# Main.net
KiCad netlist of a schematic drawn in Altium Designer
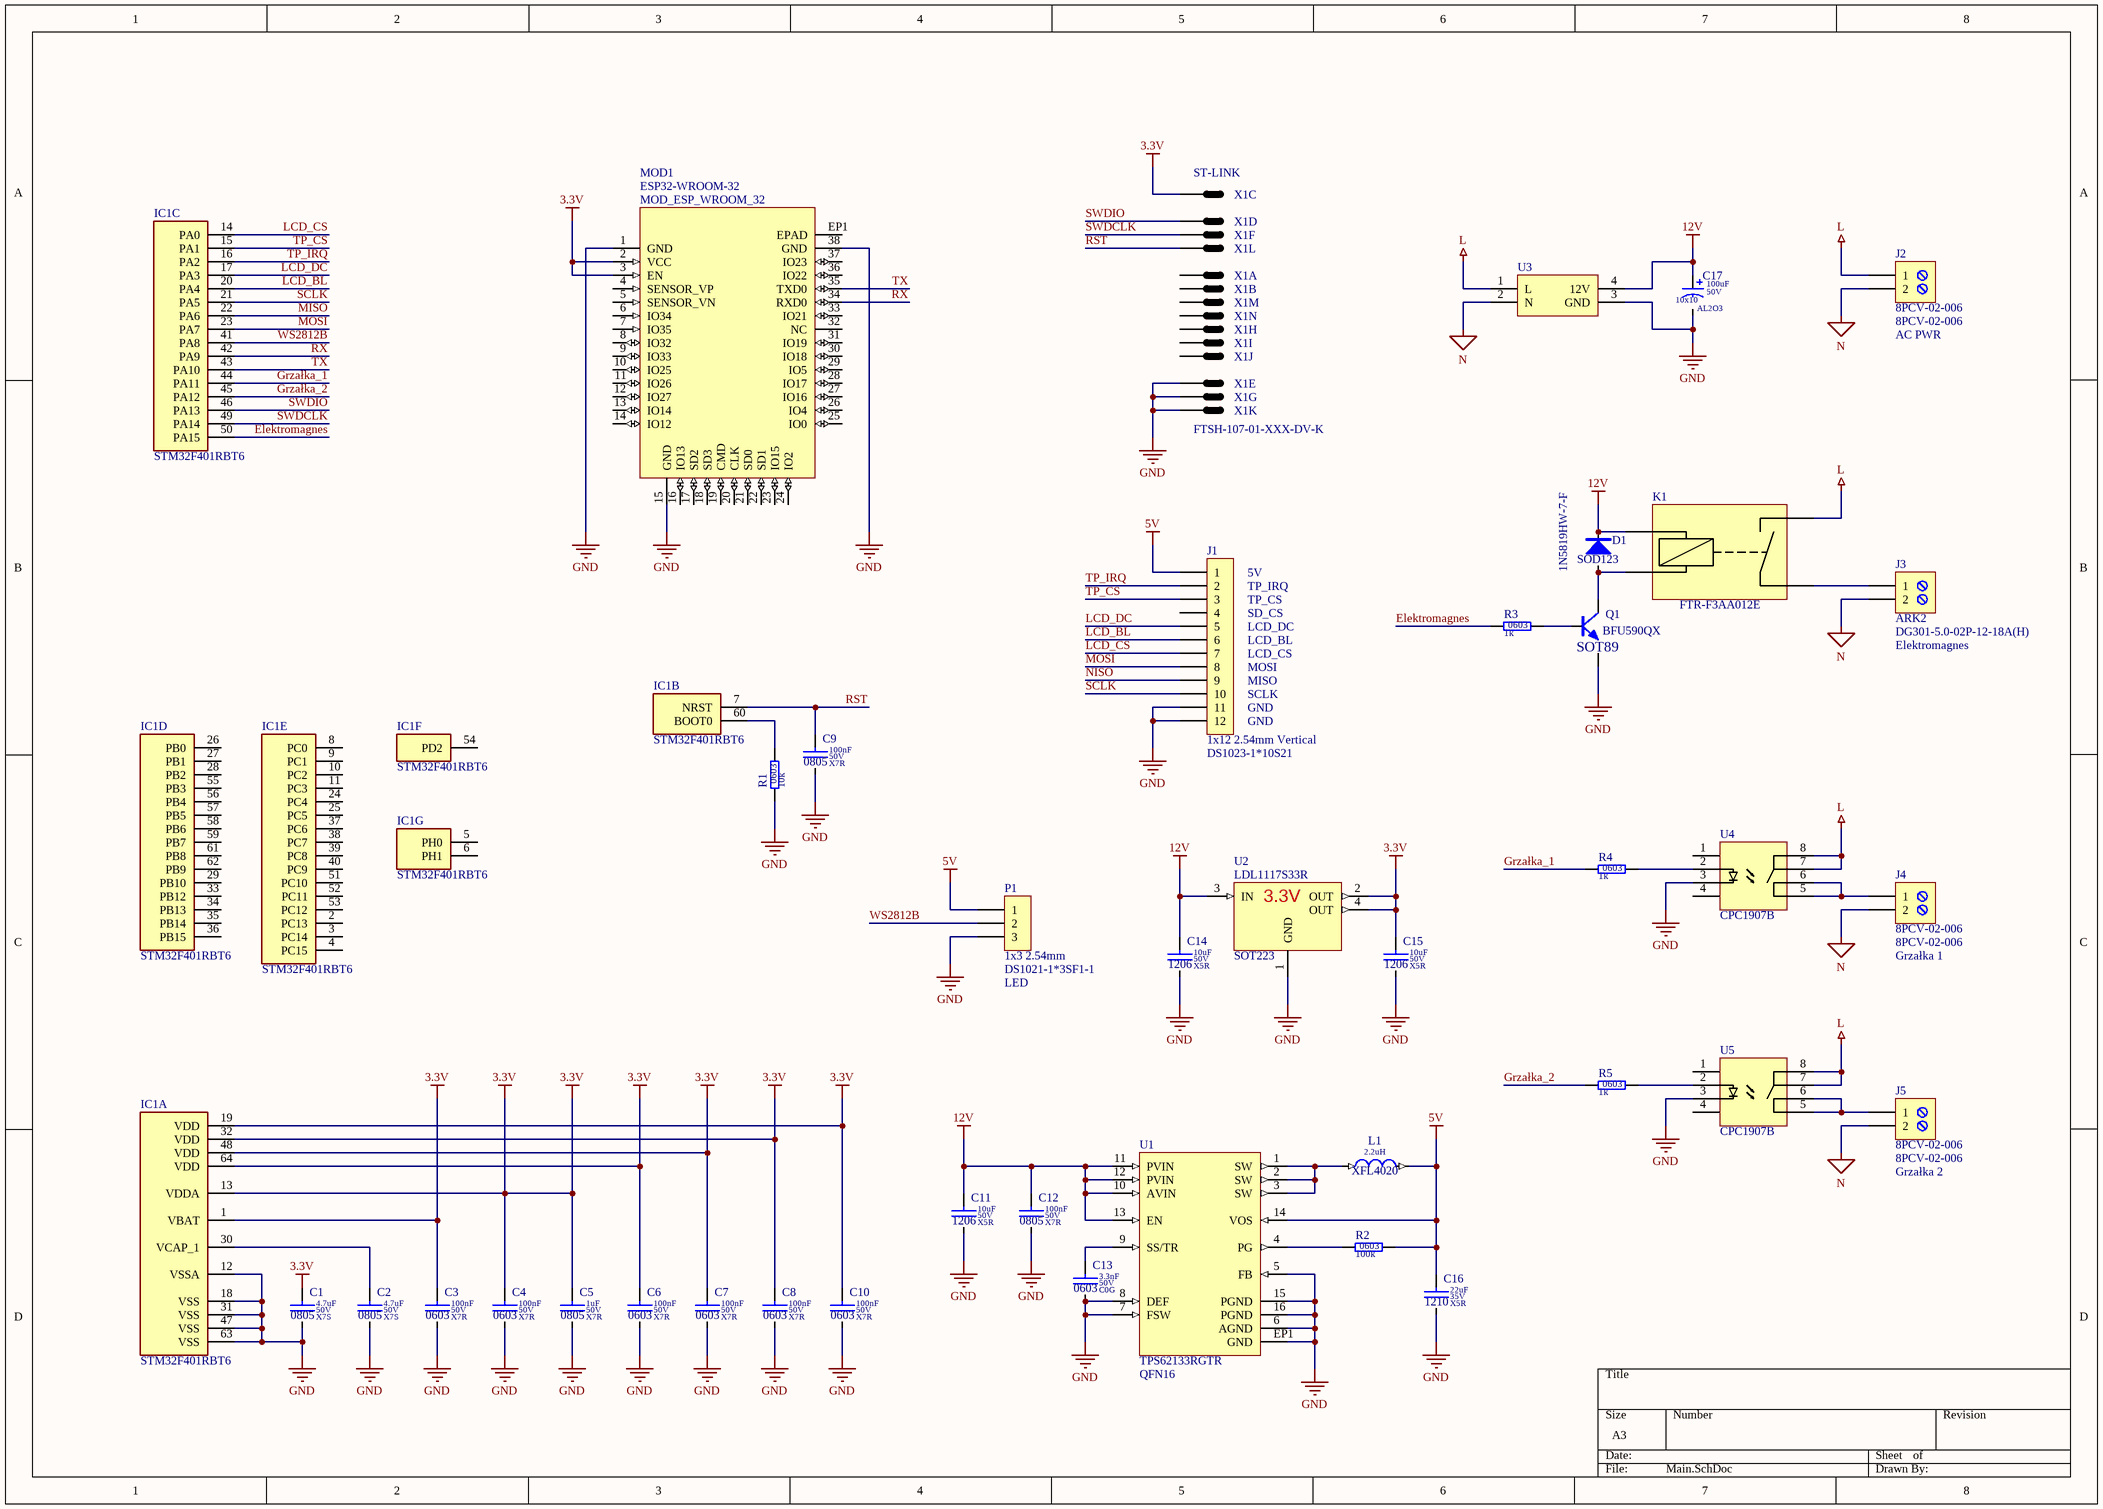
[diagram p0: Main.SchDoc]

(export (version "E")
  (design (tool "Eeschema 10.0.6"))
  (components
    (comp (ref "C1")
      (value "4.7uF")
      (footprint "C_0805_2012")
      (description "Capacitor")
      (fields
        (field (name "DIELECTRIC") "X7S")
        (field (name "VOLTAGE") "50V")
        (field (name "SCH_FOOTPRINT") "0805")
        (field (name "PART NUMBER") "C_4.7uF_50V_X7S_0805_10")
        (field (name "MANUFACTURER") "Murata")
      )
      (libsource (lib "Library") (part "C"))
    )
    (comp (ref "C2")
      (value "4.7uF")
      (footprint "C_0805_2012")
      (description "Capacitor")
      (fields
        (field (name "DIELECTRIC") "X7S")
        (field (name "VOLTAGE") "50V")
        (field (name "SCH_FOOTPRINT") "0805")
        (field (name "PART NUMBER") "C_4.7uF_50V_X7S_0805_10")
        (field (name "MANUFACTURER") "Murata")
      )
      (libsource (lib "Library") (part "C"))
    )
    (comp (ref "C3")
      (value "100nF")
      (footprint "C_0603_1608")
      (description "Capacitor")
      (fields
        (field (name "DIELECTRIC") "X7R")
        (field (name "VOLTAGE") "50V")
        (field (name "SCH_FOOTPRINT") "0603")
        (field (name "PART NUMBER") "C_100nF_50V_X7R_0603_5")
        (field (name "MANUFACTURER") "Samsung")
      )
      (libsource (lib "Library") (part "C"))
    )
    (comp (ref "C4")
      (value "100nF")
      (footprint "C_0603_1608")
      (description "Capacitor")
      (fields
        (field (name "DIELECTRIC") "X7R")
        (field (name "VOLTAGE") "50V")
        (field (name "SCH_FOOTPRINT") "0603")
        (field (name "PART NUMBER") "C_100nF_50V_X7R_0603_5")
        (field (name "MANUFACTURER") "Samsung")
      )
      (libsource (lib "Library") (part "C"))
    )
    (comp (ref "C5")
      (value "1uF")
      (footprint "C_0805_2012")
      (description "Capacitor")
      (fields
        (field (name "DIELECTRIC") "X7R")
        (field (name "VOLTAGE") "50V")
        (field (name "SCH_FOOTPRINT") "0805")
        (field (name "PART NUMBER") "C_1uF_50V_X7R_0805_10")
        (field (name "MANUFACTURER") "AVX")
      )
      (libsource (lib "Library") (part "C"))
    )
    (comp (ref "C6")
      (value "100nF")
      (footprint "C_0603_1608")
      (description "Capacitor")
      (fields
        (field (name "DIELECTRIC") "X7R")
        (field (name "VOLTAGE") "50V")
        (field (name "SCH_FOOTPRINT") "0603")
        (field (name "PART NUMBER") "C_100nF_50V_X7R_0603_5")
        (field (name "MANUFACTURER") "Samsung")
      )
      (libsource (lib "Library") (part "C"))
    )
    (comp (ref "C7")
      (value "100nF")
      (footprint "C_0603_1608")
      (description "Capacitor")
      (fields
        (field (name "DIELECTRIC") "X7R")
        (field (name "VOLTAGE") "50V")
        (field (name "SCH_FOOTPRINT") "0603")
        (field (name "PART NUMBER") "C_100nF_50V_X7R_0603_5")
        (field (name "MANUFACTURER") "Samsung")
      )
      (libsource (lib "Library") (part "C"))
    )
    (comp (ref "C8")
      (value "100nF")
      (footprint "C_0603_1608")
      (description "Capacitor")
      (fields
        (field (name "DIELECTRIC") "X7R")
        (field (name "VOLTAGE") "50V")
        (field (name "SCH_FOOTPRINT") "0603")
        (field (name "PART NUMBER") "C_100nF_50V_X7R_0603_5")
        (field (name "MANUFACTURER") "Samsung")
      )
      (libsource (lib "Library") (part "C"))
    )
    (comp (ref "C9")
      (value "100nF")
      (footprint "C_0805_2012")
      (description "Capacitor")
      (fields
        (field (name "DIELECTRIC") "X7R")
        (field (name "VOLTAGE") "50V")
        (field (name "SCH_FOOTPRINT") "0805")
        (field (name "PART NUMBER") "C_100nF_50V_X7R_0805_10")
        (field (name "MANUFACTURER") "AVX")
      )
      (libsource (lib "Library") (part "C"))
    )
    (comp (ref "C10")
      (value "100nF")
      (footprint "C_0603_1608")
      (description "Capacitor")
      (fields
        (field (name "DIELECTRIC") "X7R")
        (field (name "VOLTAGE") "50V")
        (field (name "SCH_FOOTPRINT") "0603")
        (field (name "PART NUMBER") "C_100nF_50V_X7R_0603_5")
        (field (name "MANUFACTURER") "Samsung")
      )
      (libsource (lib "Library") (part "C"))
    )
    (comp (ref "C11")
      (value "10uF")
      (footprint "C_1206_3216")
      (description "Capacitor")
      (fields
        (field (name "DIELECTRIC") "X5R")
        (field (name "VOLTAGE") "50V")
        (field (name "SCH_FOOTPRINT") "1206")
        (field (name "PART NUMBER") "C_10uF_50V_X5R_1206_10")
        (field (name "MANUFACTURER") "Murata")
      )
      (libsource (lib "Library") (part "C"))
    )
    (comp (ref "C12")
      (value "100nF")
      (footprint "C_0805_2012")
      (description "Capacitor")
      (fields
        (field (name "DIELECTRIC") "X7R")
        (field (name "VOLTAGE") "50V")
        (field (name "SCH_FOOTPRINT") "0805")
        (field (name "PART NUMBER") "C_100nF_50V_X7R_0805_10")
        (field (name "MANUFACTURER") "AVX")
      )
      (libsource (lib "Library") (part "C"))
    )
    (comp (ref "C13")
      (value "3.3nF")
      (footprint "C_0603_1608")
      (description "Capacitor")
      (fields
        (field (name "DIELECTRIC") "C0G")
        (field (name "VOLTAGE") "50V")
        (field (name "SCH_FOOTPRINT") "0603")
        (field (name "PART NUMBER") "C_3.3nF_50V_C0G_0603_5")
        (field (name "MANUFACTURER") "Murata")
      )
      (libsource (lib "Library") (part "C"))
    )
    (comp (ref "C14")
      (value "10uF")
      (footprint "C_1206_3216")
      (description "Capacitor")
      (fields
        (field (name "DIELECTRIC") "X5R")
        (field (name "VOLTAGE") "50V")
        (field (name "SCH_FOOTPRINT") "1206")
        (field (name "PART NUMBER") "C_10uF_50V_X5R_1206_10")
        (field (name "MANUFACTURER") "Murata")
      )
      (libsource (lib "Library") (part "C"))
    )
    (comp (ref "C15")
      (value "10uF")
      (footprint "C_1206_3216")
      (description "Capacitor")
      (fields
        (field (name "DIELECTRIC") "X5R")
        (field (name "VOLTAGE") "50V")
        (field (name "SCH_FOOTPRINT") "1206")
        (field (name "PART NUMBER") "C_10uF_50V_X5R_1206_10")
        (field (name "MANUFACTURER") "Murata")
      )
      (libsource (lib "Library") (part "C"))
    )
    (comp (ref "C16")
      (value "22uF")
      (footprint "C_1210_3225")
      (description "Capacitor")
      (fields
        (field (name "DIELECTRIC") "X5R")
        (field (name "VOLTAGE") "35V")
        (field (name "SCH_FOOTPRINT") "1210")
        (field (name "PART NUMBER") "C_22uF_35V_X5R_1210_20")
        (field (name "MANUFACTURER") "Taiyo Yuden")
      )
      (libsource (lib "Library") (part "C"))
    )
    (comp (ref "C17")
      (value "100uF")
      (footprint "CE_D_10x10_SMD")
      (description "Polarized Capacitor")
      (fields
        (field (name "DIELECTRIC") "AL2O3")
        (field (name "SCH_FOOTPRINT") "10x10")
        (field (name "VOLTAGE") "50V")
        (field (name "PART NUMBER") "CE_100uF_50V_AL2O3_10x10_20")
        (field (name "MANUFACTURER") "Nichicon")
      )
      (libsource (lib "Library") (part "CE"))
    )
    (comp (ref "D1")
      (value "1N5819HW-7-F")
      (footprint "SOD123")
      (fields
        (field (name "SCH_FOOTPRINT") "SOD123")
        (field (name "PART NUMBER") "D_1N5819HW_1A_40V_SOD123")
        (field (name "VOLTAGE") "40V")
        (field (name "MANUFACTURER") "Diodes Inc")
      )
      (libsource (lib "Library") (part "D"))
    )
    (comp (ref "IC1")
      (value "STM32F401RBT6")
      (footprint "LQFP-64")
      (description "ARM Microcontroller")
      (libsource (lib "Components") (part "STM32F401RBT6"))
    )
    (comp (ref "J1")
      (value "DS1023-1*10S21")
      (footprint "J_HEADER_1x12_2.54_VERTICAL")
      (description "Pin Header")
      (fields
        (field (name "SCH_FOOTPRINT") "1x12 2.54mm Vertical")
        (field (name "PART NUMBER") "J_HEADER_1x12_2.54_VERTICAL")
        (field (name "MANUFACTURER") "Connfly")
      )
      (libsource (lib "Library") (part "J_HEADER_1x12"))
    )
    (comp (ref "J2")
      (value "8PCV-02-006")
      (footprint "J_8PCV-02-006")
      (description "ARK Screw terminal, 2-Pin")
      (fields
        (field (name "SCH_FOOTPRINT") "8PCV-02-006")
        (field (name "PART NUMBER") "J_8PCV-02-006")
        (field (name "MANUFACTURER") "TE Connectivity")
      )
      (libsource (lib "Library") (part "J_ARK2"))
    )
    (comp (ref "J3")
      (value "DG301-5.0-02P-12-18A(H)")
      (footprint "J_ARK2")
      (description "ARK Screw terminal, 2-Pin")
      (fields
        (field (name "SCH_FOOTPRINT") "ARK2")
        (field (name "PART NUMBER") "J_TB-5.0-P-2P")
        (field (name "MANUFACTURER") "DEGSON ELECTRONICS")
      )
      (libsource (lib "Library") (part "J_ARK2"))
    )
    (comp (ref "J4")
      (value "8PCV-02-006")
      (footprint "J_8PCV-02-006")
      (description "ARK Screw terminal, 2-Pin")
      (fields
        (field (name "SCH_FOOTPRINT") "8PCV-02-006")
        (field (name "PART NUMBER") "J_8PCV-02-006")
        (field (name "MANUFACTURER") "TE Connectivity")
      )
      (libsource (lib "Library") (part "J_ARK2"))
    )
    (comp (ref "J5")
      (value "8PCV-02-006")
      (footprint "J_8PCV-02-006")
      (description "ARK Screw terminal, 2-Pin")
      (fields
        (field (name "SCH_FOOTPRINT") "8PCV-02-006")
        (field (name "PART NUMBER") "J_8PCV-02-006")
        (field (name "MANUFACTURER") "TE Connectivity")
      )
      (libsource (lib "Library") (part "J_ARK2"))
    )
    (comp (ref "K1")
      (value "FTR-F3AA012E")
      (footprint "FTR-F3AA012E")
      (libsource (lib "SchLib") (part "FTR-F3AA012E"))
    )
    (comp (ref "L1")
      (value "2.2uH")
      (footprint "XFL4020")
      (description "Induction")
      (fields
        (field (name "SCH_FOOTPRINT") "XFL4020")
        (field (name "PART NUMBER") "L_2.2uH_8A_XFL4020")
        (field (name "MANUFACTURER") "Coilcraft")
      )
      (libsource (lib "Library") (part "L"))
    )
    (comp (ref "MOD1")
      (value "ESP32-WROOM-32")
      (footprint "MOD_ESP_WROOM_32")
      (fields
        (field (name "SCH_FOOTPRINT") "MOD_ESP_WROOM_32")
        (field (name "PART NUMBER") "MOD_ESP32-WROOM-32")
        (field (name "MANUFACTURER") "ESPRESSIF")
        (field (name "Comment") "2.4 GHz Wi-Fi-and-Bluetooth combo chip")
      )
      (libsource (lib "Library") (part "MOD_ESP_WROOM_32"))
    )
    (comp (ref "P1")
      (value "DS1021-1*3SF1-1")
      (footprint "P_HEADER_1x3_2.54")
      (description "Pin Header")
      (fields
        (field (name "SCH_FOOTPRINT") "1x3 2.54mm")
        (field (name "PART NUMBER") "P_HEADER_1x3_2.54")
        (field (name "MANUFACTURER") "Connfly")
      )
      (libsource (lib "Library") (part "P_HEADER_1x3"))
    )
    (comp (ref "Q1")
      (value "BFU590QX")
      (footprint "SOT89_TO-243AA_N")
      (fields
        (field (name "SCH_FOOTPRINT") "SOT89")
        (field (name "PART NUMBER") "QNP_BFU590QX")
        (field (name "VOLTAGE") "12V")
        (field (name "MANUFACTURER") "NXP")
      )
      (libsource (lib "Library") (part "QNP_ECB"))
    )
    (comp (ref "R1")
      (value "10k")
      (footprint "R_0603_1608")
      (fields
        (field (name "SCH_FOOTPRINT") "0603")
        (field (name "PART NUMBER") "R_10k_0603_1")
        (field (name "VOLTAGE") "75V")
        (field (name "POWER") "100mW")
      )
      (libsource (lib "Library") (part "R"))
    )
    (comp (ref "R2")
      (value "100k")
      (footprint "R_0603_1608")
      (fields
        (field (name "SCH_FOOTPRINT") "0603")
        (field (name "PART NUMBER") "R_100k_0603_1")
        (field (name "VOLTAGE") "50V")
        (field (name "POWER") "100mW")
      )
      (libsource (lib "Library") (part "R"))
    )
    (comp (ref "R3")
      (value "1k")
      (footprint "R_0603_1608")
      (fields
        (field (name "SCH_FOOTPRINT") "0603")
        (field (name "PART NUMBER") "R_1k_0603_1")
        (field (name "VOLTAGE") "75V")
        (field (name "POWER") "100mW")
      )
      (libsource (lib "Library") (part "R"))
    )
    (comp (ref "R4")
      (value "1k")
      (footprint "R_0603_1608")
      (fields
        (field (name "SCH_FOOTPRINT") "0603")
        (field (name "PART NUMBER") "R_1k_0603_1")
        (field (name "VOLTAGE") "75V")
        (field (name "POWER") "100mW")
      )
      (libsource (lib "Library") (part "R"))
    )
    (comp (ref "R5")
      (value "1k")
      (footprint "R_0603_1608")
      (fields
        (field (name "SCH_FOOTPRINT") "0603")
        (field (name "PART NUMBER") "R_1k_0603_1")
        (field (name "VOLTAGE") "75V")
        (field (name "POWER") "100mW")
      )
      (libsource (lib "Library") (part "R"))
    )
    (comp (ref "U1")
      (value "TPS62133RGTR")
      (footprint "QFN16_3x3")
      (description "3-17V 3A Step-Down Converter with DCS-Control in 3x3 QFN")
      (fields
        (field (name "SCH_FOOTPRINT") "QFN16")
        (field (name "PART NUMBER") "VS_TPS62133RGTR")
        (field (name "MANUFACTURER") "Texas Instruments")
      )
      (libsource (lib "Library") (part "VS_TPS6213x"))
    )
    (comp (ref "U2")
      (value "LDL1117S33R")
      (footprint "SOT223_SC73")
      (description "typical configuration")
      (fields
        (field (name "SCH_FOOTPRINT") "SOT223")
        (field (name "PART NUMBER") "VL_LDL1117S33R")
        (field (name "VOLTAGE") "3.3V")
      )
      (libsource (lib "Library") (part "VL_4pin_3_1_2,4"))
    )
    (comp (ref "U3")
      (value "IRM-30-12")
      (footprint "IRM-30-12")
      (libsource (lib "SchLib") (part "IRM-30-12"))
    )
    (comp (ref "U4") (value "CPC1907B") (footprint "CPC1907B") (libsource (lib "SchLib") (part "CPC1907B")))
    (comp (ref "U5") (value "CPC1907B") (footprint "CPC1907B") (libsource (lib "SchLib") (part "CPC1907B")))
    (comp (ref "X1")
      (value "FTSH-107-01-XXX-DV-K")
      (footprint "FTSH-107-01-XXX-DV-K")
      (description "IDC 14pin male connector")
      (libsource (lib "Connectors") (part "FTSH-107-01-XXX-DV-K"))
    )
  )
  (nets
    (net (code "1") (name "/Elektromagnes") (class "Default")
      (node (ref "IC1") (pin "50") (pinfunction "PA15_50") (pintype "passive"))
      (node (ref "R3") (pin "1") (pinfunction "1_1") (pintype "passive"))
    )
    (net (code "2") (name "/Grzałka_1") (class "Default")
      (node (ref "IC1") (pin "44") (pinfunction "PA11_44") (pintype "passive"))
      (node (ref "R4") (pin "1") (pinfunction "1_1") (pintype "passive"))
    )
    (net (code "3") (name "/Grzałka_2") (class "Default")
      (node (ref "IC1") (pin "45") (pinfunction "PA12_45") (pintype "passive"))
      (node (ref "R5") (pin "1") (pinfunction "1_1") (pintype "passive"))
    )
    (net (code "4") (name "/LCD_BL") (class "Default")
      (node (ref "IC1") (pin "20") (pinfunction "PA4_20") (pintype "passive"))
      (node (ref "J1") (pin "6") (pinfunction "6_6") (pintype "passive"))
    )
    (net (code "5") (name "/LCD_CS") (class "Default")
      (node (ref "IC1") (pin "14") (pinfunction "PA0_14") (pintype "passive"))
      (node (ref "J1") (pin "7") (pinfunction "7_7") (pintype "passive"))
    )
    (net (code "6") (name "/LCD_DC") (class "Default")
      (node (ref "IC1") (pin "17") (pinfunction "PA3_17") (pintype "passive"))
      (node (ref "J1") (pin "5") (pinfunction "5_5") (pintype "passive"))
    )
    (net (code "7") (name "/MISO") (class "Default")
      (node (ref "IC1") (pin "22") (pinfunction "PA6_22") (pintype "passive"))
    )
    (net (code "8") (name "/MOSI") (class "Default")
      (node (ref "IC1") (pin "23") (pinfunction "PA7_23") (pintype "passive"))
      (node (ref "J1") (pin "8") (pinfunction "8_8") (pintype "passive"))
    )
    (net (code "9") (name "/NISO") (class "Default")
      (node (ref "J1") (pin "9") (pinfunction "9_9") (pintype "passive"))
    )
    (net (code "10") (name "/RST") (class "Default")
      (node (ref "C9") (pin "1") (pinfunction "1_1") (pintype "passive"))
      (node (ref "IC1") (pin "7") (pinfunction "NRST_7") (pintype "passive"))
      (node (ref "X1") (pin "12") (pinfunction "12_12") (pintype "passive"))
    )
    (net (code "11") (name "/RX") (class "Default")
      (node (ref "IC1") (pin "42") (pinfunction "PA9_42") (pintype "passive"))
      (node (ref "MOD1") (pin "34") (pinfunction "RXD0_34") (pintype "bidirectional"))
    )
    (net (code "12") (name "/SCLK") (class "Default")
      (node (ref "IC1") (pin "21") (pinfunction "PA5_21") (pintype "passive"))
      (node (ref "J1") (pin "10") (pinfunction "10_10") (pintype "passive"))
    )
    (net (code "13") (name "/SWDCLK") (class "Default")
      (node (ref "IC1") (pin "49") (pinfunction "PA14_49") (pintype "passive"))
      (node (ref "X1") (pin "6") (pinfunction "6_6") (pintype "passive"))
    )
    (net (code "14") (name "/SWDIO") (class "Default")
      (node (ref "IC1") (pin "46") (pinfunction "PA13_46") (pintype "passive"))
      (node (ref "X1") (pin "4") (pinfunction "4_4") (pintype "passive"))
    )
    (net (code "15") (name "/TP_CS") (class "Default")
      (node (ref "IC1") (pin "15") (pinfunction "PA1_15") (pintype "passive"))
      (node (ref "J1") (pin "3") (pinfunction "3_3") (pintype "passive"))
    )
    (net (code "16") (name "/TP_IRQ") (class "Default")
      (node (ref "IC1") (pin "16") (pinfunction "PA2_16") (pintype "passive"))
      (node (ref "J1") (pin "2") (pinfunction "2_2") (pintype "passive"))
    )
    (net (code "17") (name "/TX") (class "Default")
      (node (ref "IC1") (pin "43") (pinfunction "PA10_43") (pintype "passive"))
      (node (ref "MOD1") (pin "35") (pinfunction "TXD0_35") (pintype "bidirectional"))
    )
    (net (code "18") (name "/WS2812B") (class "Default")
      (node (ref "IC1") (pin "41") (pinfunction "PA8_41") (pintype "passive"))
      (node (ref "P1") (pin "2") (pinfunction "2_2") (pintype "passive"))
    )
    (net (code "19") (name "3.3V") (class "Default")
      (node (ref "C1") (pin "1") (pinfunction "1_1") (pintype "passive"))
      (node (ref "C10") (pin "1") (pinfunction "1_1") (pintype "passive"))
      (node (ref "C15") (pin "1") (pinfunction "1_1") (pintype "passive"))
      (node (ref "C3") (pin "1") (pinfunction "1_1") (pintype "passive"))
      (node (ref "C4") (pin "1") (pinfunction "1_1") (pintype "passive"))
      (node (ref "C5") (pin "1") (pinfunction "1_1") (pintype "passive"))
      (node (ref "C6") (pin "1") (pinfunction "1_1") (pintype "passive"))
      (node (ref "C7") (pin "1") (pinfunction "1_1") (pintype "passive"))
      (node (ref "C8") (pin "1") (pinfunction "1_1") (pintype "passive"))
      (node (ref "IC1") (pin "1") (pinfunction "VBAT_1") (pintype "passive"))
      (node (ref "IC1") (pin "13") (pinfunction "VDDA_13") (pintype "passive"))
      (node (ref "IC1") (pin "19") (pinfunction "VDD_19") (pintype "passive"))
      (node (ref "IC1") (pin "32") (pinfunction "VDD_32") (pintype "passive"))
      (node (ref "IC1") (pin "48") (pinfunction "VDD_48") (pintype "passive"))
      (node (ref "IC1") (pin "64") (pinfunction "VDD_64") (pintype "passive"))
      (node (ref "MOD1") (pin "2") (pinfunction "VCC_2") (pintype "input"))
      (node (ref "MOD1") (pin "3") (pinfunction "EN_3") (pintype "input"))
      (node (ref "U2") (pin "2") (pinfunction "OUT_2") (pintype "output"))
      (node (ref "U2") (pin "4") (pinfunction "OUT_4") (pintype "output"))
      (node (ref "X1") (pin "3") (pinfunction "3_3") (pintype "passive"))
    )
    (net (code "20") (name "5V") (class "Default")
      (node (ref "C16") (pin "1") (pinfunction "1_1") (pintype "passive"))
      (node (ref "J1") (pin "1") (pinfunction "1_1") (pintype "passive"))
      (node (ref "L1") (pin "2") (pinfunction "2_2") (pintype "output"))
      (node (ref "P1") (pin "1") (pinfunction "1_1") (pintype "passive"))
      (node (ref "R2") (pin "2") (pinfunction "2_2") (pintype "passive"))
      (node (ref "U1") (pin "14") (pinfunction "VOS_14") (pintype "input"))
    )
    (net (code "21") (name "12V") (class "Default")
      (node (ref "C11") (pin "1") (pinfunction "1_1") (pintype "passive"))
      (node (ref "C12") (pin "1") (pinfunction "1_1") (pintype "passive"))
      (node (ref "C14") (pin "1") (pinfunction "1_1") (pintype "passive"))
      (node (ref "C17") (pin "1") (pinfunction "1_1") (pintype "passive"))
      (node (ref "D1") (pin "1") (pintype "passive"))
      (node (ref "K1") (pin "1") (pinfunction "1_1") (pintype "passive"))
      (node (ref "U1") (pin "10") (pinfunction "AVIN_10") (pintype "input"))
      (node (ref "U1") (pin "11") (pinfunction "PVIN_11") (pintype "input"))
      (node (ref "U1") (pin "12") (pinfunction "PVIN_12") (pintype "input"))
      (node (ref "U1") (pin "13") (pinfunction "EN_13") (pintype "input"))
      (node (ref "U2") (pin "3") (pinfunction "IN_3") (pintype "input"))
      (node (ref "U3") (pin "4") (pinfunction "12V_4") (pintype "passive"))
    )
    (net (code "22") (name "GND") (class "Default")
      (node (ref "C1") (pin "2") (pinfunction "2_2") (pintype "passive"))
      (node (ref "C10") (pin "2") (pinfunction "2_2") (pintype "passive"))
      (node (ref "C11") (pin "2") (pinfunction "2_2") (pintype "passive"))
      (node (ref "C12") (pin "2") (pinfunction "2_2") (pintype "passive"))
      (node (ref "C13") (pin "2") (pinfunction "2_2") (pintype "passive"))
      (node (ref "C14") (pin "2") (pinfunction "2_2") (pintype "passive"))
      (node (ref "C15") (pin "2") (pinfunction "2_2") (pintype "passive"))
      (node (ref "C16") (pin "2") (pinfunction "2_2") (pintype "passive"))
      (node (ref "C17") (pin "2") (pinfunction "2_2") (pintype "passive"))
      (node (ref "C2") (pin "2") (pinfunction "2_2") (pintype "passive"))
      (node (ref "C3") (pin "2") (pinfunction "2_2") (pintype "passive"))
      (node (ref "C4") (pin "2") (pinfunction "2_2") (pintype "passive"))
      (node (ref "C5") (pin "2") (pinfunction "2_2") (pintype "passive"))
      (node (ref "C6") (pin "2") (pinfunction "2_2") (pintype "passive"))
      (node (ref "C7") (pin "2") (pinfunction "2_2") (pintype "passive"))
      (node (ref "C8") (pin "2") (pinfunction "2_2") (pintype "passive"))
      (node (ref "C9") (pin "2") (pinfunction "2_2") (pintype "passive"))
      (node (ref "IC1") (pin "12") (pinfunction "VSSA_12") (pintype "passive"))
      (node (ref "IC1") (pin "18") (pinfunction "VSS_18") (pintype "passive"))
      (node (ref "IC1") (pin "31") (pinfunction "VSS_31") (pintype "passive"))
      (node (ref "IC1") (pin "47") (pinfunction "VSS_47") (pintype "passive"))
      (node (ref "IC1") (pin "63") (pinfunction "VSS_63") (pintype "passive"))
      (node (ref "J1") (pin "11") (pinfunction "11_11") (pintype "passive"))
      (node (ref "J1") (pin "12") (pinfunction "12_12") (pintype "passive"))
      (node (ref "MOD1") (pin "1") (pinfunction "GND_1") (pintype "power_in"))
      (node (ref "MOD1") (pin "15") (pinfunction "GND_15") (pintype "power_in"))
      (node (ref "MOD1") (pin "38") (pinfunction "GND_38") (pintype "power_in"))
      (node (ref "P1") (pin "3") (pinfunction "3_3") (pintype "passive"))
      (node (ref "Q1") (pin "1") (pinfunction "E_1") (pintype "passive"))
      (node (ref "R1") (pin "1") (pinfunction "1_1") (pintype "passive"))
      (node (ref "U1") (pin "15") (pinfunction "PGND_15") (pintype "power_in"))
      (node (ref "U1") (pin "16") (pinfunction "PGND_16") (pintype "power_in"))
      (node (ref "U1") (pin "5") (pinfunction "FB_5") (pintype "input"))
      (node (ref "U1") (pin "6") (pinfunction "AGND_6") (pintype "power_in"))
      (node (ref "U1") (pin "7") (pinfunction "FSW_7") (pintype "input"))
      (node (ref "U1") (pin "8") (pinfunction "DEF_8") (pintype "input"))
      (node (ref "U1") (pin "EP1") (pinfunction "GND_EP1") (pintype "power_in"))
      (node (ref "U2") (pin "1") (pinfunction "GND_1") (pintype "power_in"))
      (node (ref "U3") (pin "3") (pinfunction "GND_3") (pintype "passive"))
      (node (ref "U4") (pin "3") (pinfunction "3_3") (pintype "passive"))
      (node (ref "U5") (pin "3") (pinfunction "3_3") (pintype "passive"))
      (node (ref "X1") (pin "11") (pinfunction "11_11") (pintype "passive"))
      (node (ref "X1") (pin "5") (pinfunction "5_5") (pintype "passive"))
      (node (ref "X1") (pin "7") (pinfunction "7_7") (pintype "passive"))
    )
    (net (code "23") (name "L") (class "Default")
      (node (ref "J2") (pin "1") (pinfunction "1_1") (pintype "passive"))
      (node (ref "K1") (pin "3") (pinfunction "3_3") (pintype "passive"))
      (node (ref "U3") (pin "1") (pinfunction "L_1") (pintype "passive"))
      (node (ref "U4") (pin "7") (pinfunction "7_7") (pintype "passive"))
      (node (ref "U4") (pin "8") (pinfunction "8_8") (pintype "passive"))
      (node (ref "U5") (pin "7") (pinfunction "7_7") (pintype "passive"))
      (node (ref "U5") (pin "8") (pinfunction "8_8") (pintype "passive"))
    )
    (net (code "24") (name "N") (class "Default")
      (node (ref "J2") (pin "2") (pinfunction "2_2") (pintype "passive"))
      (node (ref "J3") (pin "2") (pinfunction "2_2") (pintype "passive"))
      (node (ref "J4") (pin "2") (pinfunction "2_2") (pintype "passive"))
      (node (ref "J5") (pin "2") (pinfunction "2_2") (pintype "passive"))
      (node (ref "U3") (pin "2") (pinfunction "N_2") (pintype "passive"))
    )
    (net (code "25") (name "Net-(IC1A-VCAP_1)") (class "Default")
      (node (ref "C2") (pin "1") (pinfunction "1_1") (pintype "passive"))
      (node (ref "IC1") (pin "30") (pinfunction "VCAP_1_30") (pintype "passive"))
    )
    (net (code "26") (name "Net-(IC1B-BOOT0)") (class "Default")
      (node (ref "IC1") (pin "60") (pinfunction "BOOT0_60") (pintype "passive"))
      (node (ref "R1") (pin "2") (pinfunction "2_2") (pintype "passive"))
    )
    (net (code "27") (name "Net-(J3-Pad1)") (class "Default")
      (node (ref "J3") (pin "1") (pinfunction "1_1") (pintype "passive"))
      (node (ref "K1") (pin "4") (pinfunction "4_4") (pintype "passive"))
    )
    (net (code "28") (name "Net-(J4-Pad1)") (class "Default")
      (node (ref "J4") (pin "1") (pinfunction "1_1") (pintype "passive"))
      (node (ref "U4") (pin "5") (pinfunction "5_5") (pintype "passive"))
      (node (ref "U4") (pin "6") (pinfunction "6_6") (pintype "passive"))
    )
    (net (code "29") (name "Net-(J5-Pad1)") (class "Default")
      (node (ref "J5") (pin "1") (pinfunction "1_1") (pintype "passive"))
      (node (ref "U5") (pin "5") (pinfunction "5_5") (pintype "passive"))
      (node (ref "U5") (pin "6") (pinfunction "6_6") (pintype "passive"))
    )
    (net (code "30") (name "Net-(L1-Pad1)") (class "Default")
      (node (ref "L1") (pin "1") (pinfunction "1_1") (pintype "input"))
      (node (ref "U1") (pin "1") (pinfunction "SW_1") (pintype "output"))
      (node (ref "U1") (pin "2") (pinfunction "SW_2") (pintype "output"))
      (node (ref "U1") (pin "3") (pinfunction "SW_3") (pintype "output"))
    )
    (net (code "31") (name "Net-(Q1-B)") (class "Default")
      (node (ref "Q1") (pin "3") (pinfunction "B_3") (pintype "passive"))
      (node (ref "R3") (pin "2") (pinfunction "2_2") (pintype "passive"))
    )
    (net (code "32") (name "Net-(Q1-C)") (class "Default")
      (node (ref "D1") (pin "2") (pintype "passive"))
      (node (ref "K1") (pin "2") (pinfunction "2_2") (pintype "passive"))
      (node (ref "Q1") (pin "2") (pinfunction "C_2") (pintype "passive"))
    )
    (net (code "33") (name "Net-(R4-Pad2)") (class "Default")
      (node (ref "R4") (pin "2") (pinfunction "2_2") (pintype "passive"))
      (node (ref "U4") (pin "2") (pinfunction "2_2") (pintype "passive"))
    )
    (net (code "34") (name "Net-(R5-Pad2)") (class "Default")
      (node (ref "R5") (pin "2") (pinfunction "2_2") (pintype "passive"))
      (node (ref "U5") (pin "2") (pinfunction "2_2") (pintype "passive"))
    )
    (net (code "35") (name "Net-(U1-PG)") (class "Default")
      (node (ref "R2") (pin "1") (pinfunction "1_1") (pintype "passive"))
      (node (ref "U1") (pin "4") (pinfunction "PG_4") (pintype "output"))
    )
    (net (code "36") (name "Net-(U1-SS{slash}TR)") (class "Default")
      (node (ref "C13") (pin "1") (pinfunction "1_1") (pintype "passive"))
      (node (ref "U1") (pin "9") (pinfunction "SS/TR_9") (pintype "input"))
    )
    (net (code "37") (name "unconnected-(IC1D-PB0-Pad26)") (class "Default")
      (node (ref "IC1") (pin "26") (pinfunction "PB0_26") (pintype "passive"))
    )
    (net (code "38") (name "unconnected-(IC1D-PB1-Pad27)") (class "Default")
      (node (ref "IC1") (pin "27") (pinfunction "PB1_27") (pintype "passive"))
    )
    (net (code "39") (name "unconnected-(IC1D-PB2-Pad28)") (class "Default")
      (node (ref "IC1") (pin "28") (pinfunction "PB2_28") (pintype "passive"))
    )
    (net (code "40") (name "unconnected-(IC1D-PB3-Pad55)") (class "Default")
      (node (ref "IC1") (pin "55") (pinfunction "PB3_55") (pintype "passive"))
    )
    (net (code "41") (name "unconnected-(IC1D-PB4-Pad56)") (class "Default")
      (node (ref "IC1") (pin "56") (pinfunction "PB4_56") (pintype "passive"))
    )
    (net (code "42") (name "unconnected-(IC1D-PB5-Pad57)") (class "Default")
      (node (ref "IC1") (pin "57") (pinfunction "PB5_57") (pintype "passive"))
    )
    (net (code "43") (name "unconnected-(IC1D-PB6-Pad58)") (class "Default")
      (node (ref "IC1") (pin "58") (pinfunction "PB6_58") (pintype "passive"))
    )
    (net (code "44") (name "unconnected-(IC1D-PB7-Pad59)") (class "Default")
      (node (ref "IC1") (pin "59") (pinfunction "PB7_59") (pintype "passive"))
    )
    (net (code "45") (name "unconnected-(IC1D-PB8-Pad61)") (class "Default")
      (node (ref "IC1") (pin "61") (pinfunction "PB8_61") (pintype "passive"))
    )
    (net (code "46") (name "unconnected-(IC1D-PB9-Pad62)") (class "Default")
      (node (ref "IC1") (pin "62") (pinfunction "PB9_62") (pintype "passive"))
    )
    (net (code "47") (name "unconnected-(IC1D-PB10-Pad29)") (class "Default")
      (node (ref "IC1") (pin "29") (pinfunction "PB10_29") (pintype "passive"))
    )
    (net (code "48") (name "unconnected-(IC1D-PB12-Pad33)") (class "Default")
      (node (ref "IC1") (pin "33") (pinfunction "PB12_33") (pintype "passive"))
    )
    (net (code "49") (name "unconnected-(IC1D-PB13-Pad34)") (class "Default")
      (node (ref "IC1") (pin "34") (pinfunction "PB13_34") (pintype "passive"))
    )
    (net (code "50") (name "unconnected-(IC1D-PB14-Pad35)") (class "Default")
      (node (ref "IC1") (pin "35") (pinfunction "PB14_35") (pintype "passive"))
    )
    (net (code "51") (name "unconnected-(IC1D-PB15-Pad36)") (class "Default")
      (node (ref "IC1") (pin "36") (pinfunction "PB15_36") (pintype "passive"))
    )
    (net (code "52") (name "unconnected-(IC1E-PC0-Pad8)") (class "Default")
      (node (ref "IC1") (pin "8") (pinfunction "PC0_8") (pintype "passive"))
    )
    (net (code "53") (name "unconnected-(IC1E-PC1-Pad9)") (class "Default")
      (node (ref "IC1") (pin "9") (pinfunction "PC1_9") (pintype "passive"))
    )
    (net (code "54") (name "unconnected-(IC1E-PC2-Pad10)") (class "Default")
      (node (ref "IC1") (pin "10") (pinfunction "PC2_10") (pintype "passive"))
    )
    (net (code "55") (name "unconnected-(IC1E-PC3-Pad11)") (class "Default")
      (node (ref "IC1") (pin "11") (pinfunction "PC3_11") (pintype "passive"))
    )
    (net (code "56") (name "unconnected-(IC1E-PC4-Pad24)") (class "Default")
      (node (ref "IC1") (pin "24") (pinfunction "PC4_24") (pintype "passive"))
    )
    (net (code "57") (name "unconnected-(IC1E-PC5-Pad25)") (class "Default")
      (node (ref "IC1") (pin "25") (pinfunction "PC5_25") (pintype "passive"))
    )
    (net (code "58") (name "unconnected-(IC1E-PC6-Pad37)") (class "Default")
      (node (ref "IC1") (pin "37") (pinfunction "PC6_37") (pintype "passive"))
    )
    (net (code "59") (name "unconnected-(IC1E-PC7-Pad38)") (class "Default")
      (node (ref "IC1") (pin "38") (pinfunction "PC7_38") (pintype "passive"))
    )
    (net (code "60") (name "unconnected-(IC1E-PC8-Pad39)") (class "Default")
      (node (ref "IC1") (pin "39") (pinfunction "PC8_39") (pintype "passive"))
    )
    (net (code "61") (name "unconnected-(IC1E-PC9-Pad40)") (class "Default")
      (node (ref "IC1") (pin "40") (pinfunction "PC9_40") (pintype "passive"))
    )
    (net (code "62") (name "unconnected-(IC1E-PC10-Pad51)") (class "Default")
      (node (ref "IC1") (pin "51") (pinfunction "PC10_51") (pintype "passive"))
    )
    (net (code "63") (name "unconnected-(IC1E-PC11-Pad52)") (class "Default")
      (node (ref "IC1") (pin "52") (pinfunction "PC11_52") (pintype "passive"))
    )
    (net (code "64") (name "unconnected-(IC1E-PC12-Pad53)") (class "Default")
      (node (ref "IC1") (pin "53") (pinfunction "PC12_53") (pintype "passive"))
    )
    (net (code "65") (name "unconnected-(IC1E-PC13-Pad2)") (class "Default")
      (node (ref "IC1") (pin "2") (pinfunction "PC13_2") (pintype "passive"))
    )
    (net (code "66") (name "unconnected-(IC1E-PC14-Pad3)") (class "Default")
      (node (ref "IC1") (pin "3") (pinfunction "PC14_3") (pintype "passive"))
    )
    (net (code "67") (name "unconnected-(IC1E-PC15-Pad4)") (class "Default")
      (node (ref "IC1") (pin "4") (pinfunction "PC15_4") (pintype "passive"))
    )
    (net (code "68") (name "unconnected-(IC1F-PD2-Pad54)") (class "Default")
      (node (ref "IC1") (pin "54") (pinfunction "PD2_54") (pintype "passive"))
    )
    (net (code "69") (name "unconnected-(IC1G-PH0-Pad5)") (class "Default")
      (node (ref "IC1") (pin "5") (pinfunction "PH0_5") (pintype "passive"))
    )
    (net (code "70") (name "unconnected-(IC1G-PH1-Pad6)") (class "Default")
      (node (ref "IC1") (pin "6") (pinfunction "PH1_6") (pintype "passive"))
    )
    (net (code "71") (name "unconnected-(J1-Pad4)") (class "Default")
      (node (ref "J1") (pin "4") (pinfunction "4_4") (pintype "passive"))
    )
    (net (code "72") (name "unconnected-(MOD1-CLK-Pad20)") (class "Default")
      (node (ref "MOD1") (pin "20") (pinfunction "CLK_20") (pintype "bidirectional"))
    )
    (net (code "73") (name "unconnected-(MOD1-CMD-Pad19)") (class "Default")
      (node (ref "MOD1") (pin "19") (pinfunction "CMD_19") (pintype "bidirectional"))
    )
    (net (code "74") (name "unconnected-(MOD1-EPAD-PadEP1)") (class "Default")
      (node (ref "MOD1") (pin "EP1") (pinfunction "EPAD_EP1") (pintype "power_in"))
    )
    (net (code "75") (name "unconnected-(MOD1-IO0-Pad25)") (class "Default")
      (node (ref "MOD1") (pin "25") (pinfunction "IO0_25") (pintype "bidirectional"))
    )
    (net (code "76") (name "unconnected-(MOD1-IO2-Pad24)") (class "Default")
      (node (ref "MOD1") (pin "24") (pinfunction "IO2_24") (pintype "bidirectional"))
    )
    (net (code "77") (name "unconnected-(MOD1-IO4-Pad26)") (class "Default")
      (node (ref "MOD1") (pin "26") (pinfunction "IO4_26") (pintype "bidirectional"))
    )
    (net (code "78") (name "unconnected-(MOD1-IO5-Pad29)") (class "Default")
      (node (ref "MOD1") (pin "29") (pinfunction "IO5_29") (pintype "bidirectional"))
    )
    (net (code "79") (name "unconnected-(MOD1-IO12-Pad14)") (class "Default")
      (node (ref "MOD1") (pin "14") (pinfunction "IO12_14") (pintype "bidirectional"))
    )
    (net (code "80") (name "unconnected-(MOD1-IO13-Pad16)") (class "Default")
      (node (ref "MOD1") (pin "16") (pinfunction "IO13_16") (pintype "bidirectional"))
    )
    (net (code "81") (name "unconnected-(MOD1-IO14-Pad13)") (class "Default")
      (node (ref "MOD1") (pin "13") (pinfunction "IO14_13") (pintype "bidirectional"))
    )
    (net (code "82") (name "unconnected-(MOD1-IO15-Pad23)") (class "Default")
      (node (ref "MOD1") (pin "23") (pinfunction "IO15_23") (pintype "bidirectional"))
    )
    (net (code "83") (name "unconnected-(MOD1-IO16-Pad27)") (class "Default")
      (node (ref "MOD1") (pin "27") (pinfunction "IO16_27") (pintype "bidirectional"))
    )
    (net (code "84") (name "unconnected-(MOD1-IO17-Pad28)") (class "Default")
      (node (ref "MOD1") (pin "28") (pinfunction "IO17_28") (pintype "bidirectional"))
    )
    (net (code "85") (name "unconnected-(MOD1-IO18-Pad30)") (class "Default")
      (node (ref "MOD1") (pin "30") (pinfunction "IO18_30") (pintype "bidirectional"))
    )
    (net (code "86") (name "unconnected-(MOD1-IO19-Pad31)") (class "Default")
      (node (ref "MOD1") (pin "31") (pinfunction "IO19_31") (pintype "bidirectional"))
    )
    (net (code "87") (name "unconnected-(MOD1-IO21-Pad33)") (class "Default")
      (node (ref "MOD1") (pin "33") (pinfunction "IO21_33") (pintype "bidirectional"))
    )
    (net (code "88") (name "unconnected-(MOD1-IO22-Pad36)") (class "Default")
      (node (ref "MOD1") (pin "36") (pinfunction "IO22_36") (pintype "bidirectional"))
    )
    (net (code "89") (name "unconnected-(MOD1-IO23-Pad37)") (class "Default")
      (node (ref "MOD1") (pin "37") (pinfunction "IO23_37") (pintype "bidirectional"))
    )
    (net (code "90") (name "unconnected-(MOD1-IO25-Pad10)") (class "Default")
      (node (ref "MOD1") (pin "10") (pinfunction "IO25_10") (pintype "bidirectional"))
    )
    (net (code "91") (name "unconnected-(MOD1-IO26-Pad11)") (class "Default")
      (node (ref "MOD1") (pin "11") (pinfunction "IO26_11") (pintype "bidirectional"))
    )
    (net (code "92") (name "unconnected-(MOD1-IO27-Pad12)") (class "Default")
      (node (ref "MOD1") (pin "12") (pinfunction "IO27_12") (pintype "bidirectional"))
    )
    (net (code "93") (name "unconnected-(MOD1-IO32-Pad8)") (class "Default")
      (node (ref "MOD1") (pin "8") (pinfunction "IO32_8") (pintype "bidirectional"))
    )
    (net (code "94") (name "unconnected-(MOD1-IO33-Pad9)") (class "Default")
      (node (ref "MOD1") (pin "9") (pinfunction "IO33_9") (pintype "bidirectional"))
    )
    (net (code "95") (name "unconnected-(MOD1-IO34-Pad6)") (class "Default")
      (node (ref "MOD1") (pin "6") (pinfunction "IO34_6") (pintype "input"))
    )
    (net (code "96") (name "unconnected-(MOD1-IO35-Pad7)") (class "Default")
      (node (ref "MOD1") (pin "7") (pinfunction "IO35_7") (pintype "input"))
    )
    (net (code "97") (name "unconnected-(MOD1-NC-Pad32)") (class "Default")
      (node (ref "MOD1") (pin "32") (pinfunction "NC_32") (pintype "passive"))
    )
    (net (code "98") (name "unconnected-(MOD1-SD0-Pad21)") (class "Default")
      (node (ref "MOD1") (pin "21") (pinfunction "SD0_21") (pintype "bidirectional"))
    )
    (net (code "99") (name "unconnected-(MOD1-SD1-Pad22)") (class "Default")
      (node (ref "MOD1") (pin "22") (pinfunction "SD1_22") (pintype "bidirectional"))
    )
    (net (code "100") (name "unconnected-(MOD1-SD2-Pad17)") (class "Default")
      (node (ref "MOD1") (pin "17") (pinfunction "SD2_17") (pintype "bidirectional"))
    )
    (net (code "101") (name "unconnected-(MOD1-SD3-Pad18)") (class "Default")
      (node (ref "MOD1") (pin "18") (pinfunction "SD3_18") (pintype "bidirectional"))
    )
    (net (code "102") (name "unconnected-(MOD1-SENSOR_VN-Pad5)") (class "Default")
      (node (ref "MOD1") (pin "5") (pinfunction "SENSOR_VN_5") (pintype "input"))
    )
    (net (code "103") (name "unconnected-(MOD1-SENSOR_VP-Pad4)") (class "Default")
      (node (ref "MOD1") (pin "4") (pinfunction "SENSOR_VP_4") (pintype "input"))
    )
    (net (code "104") (name "unconnected-(U4-Pad1)") (class "Default")
      (node (ref "U4") (pin "1") (pinfunction "1_1") (pintype "passive"))
    )
    (net (code "105") (name "unconnected-(U4-Pad4)") (class "Default")
      (node (ref "U4") (pin "4") (pinfunction "4_4") (pintype "passive"))
    )
    (net (code "106") (name "unconnected-(U5-Pad1)") (class "Default")
      (node (ref "U5") (pin "1") (pinfunction "1_1") (pintype "passive"))
    )
    (net (code "107") (name "unconnected-(U5-Pad4)") (class "Default")
      (node (ref "U5") (pin "4") (pinfunction "4_4") (pintype "passive"))
    )
    (net (code "108") (name "unconnected-(X1-Pad1)") (class "Default")
      (node (ref "X1") (pin "1") (pinfunction "1_1") (pintype "passive"))
    )
    (net (code "109") (name "unconnected-(X1-Pad2)") (class "Default")
      (node (ref "X1") (pin "2") (pinfunction "2_2") (pintype "passive"))
    )
    (net (code "110") (name "unconnected-(X1-Pad8)") (class "Default")
      (node (ref "X1") (pin "8") (pinfunction "8_8") (pintype "passive"))
    )
    (net (code "111") (name "unconnected-(X1-Pad9)") (class "Default")
      (node (ref "X1") (pin "9") (pinfunction "9_9") (pintype "passive"))
    )
    (net (code "112") (name "unconnected-(X1-Pad10)") (class "Default")
      (node (ref "X1") (pin "10") (pinfunction "10_10") (pintype "passive"))
    )
    (net (code "113") (name "unconnected-(X1-Pad13)") (class "Default")
      (node (ref "X1") (pin "13") (pinfunction "13_13") (pintype "passive"))
    )
    (net (code "114") (name "unconnected-(X1-Pad14)") (class "Default")
      (node (ref "X1") (pin "14") (pinfunction "14_14") (pintype "passive"))
    )
  )
)
